# MRCS-Occupancy-Display.net
KiCad netlist of a schematic drawn in EAGLE
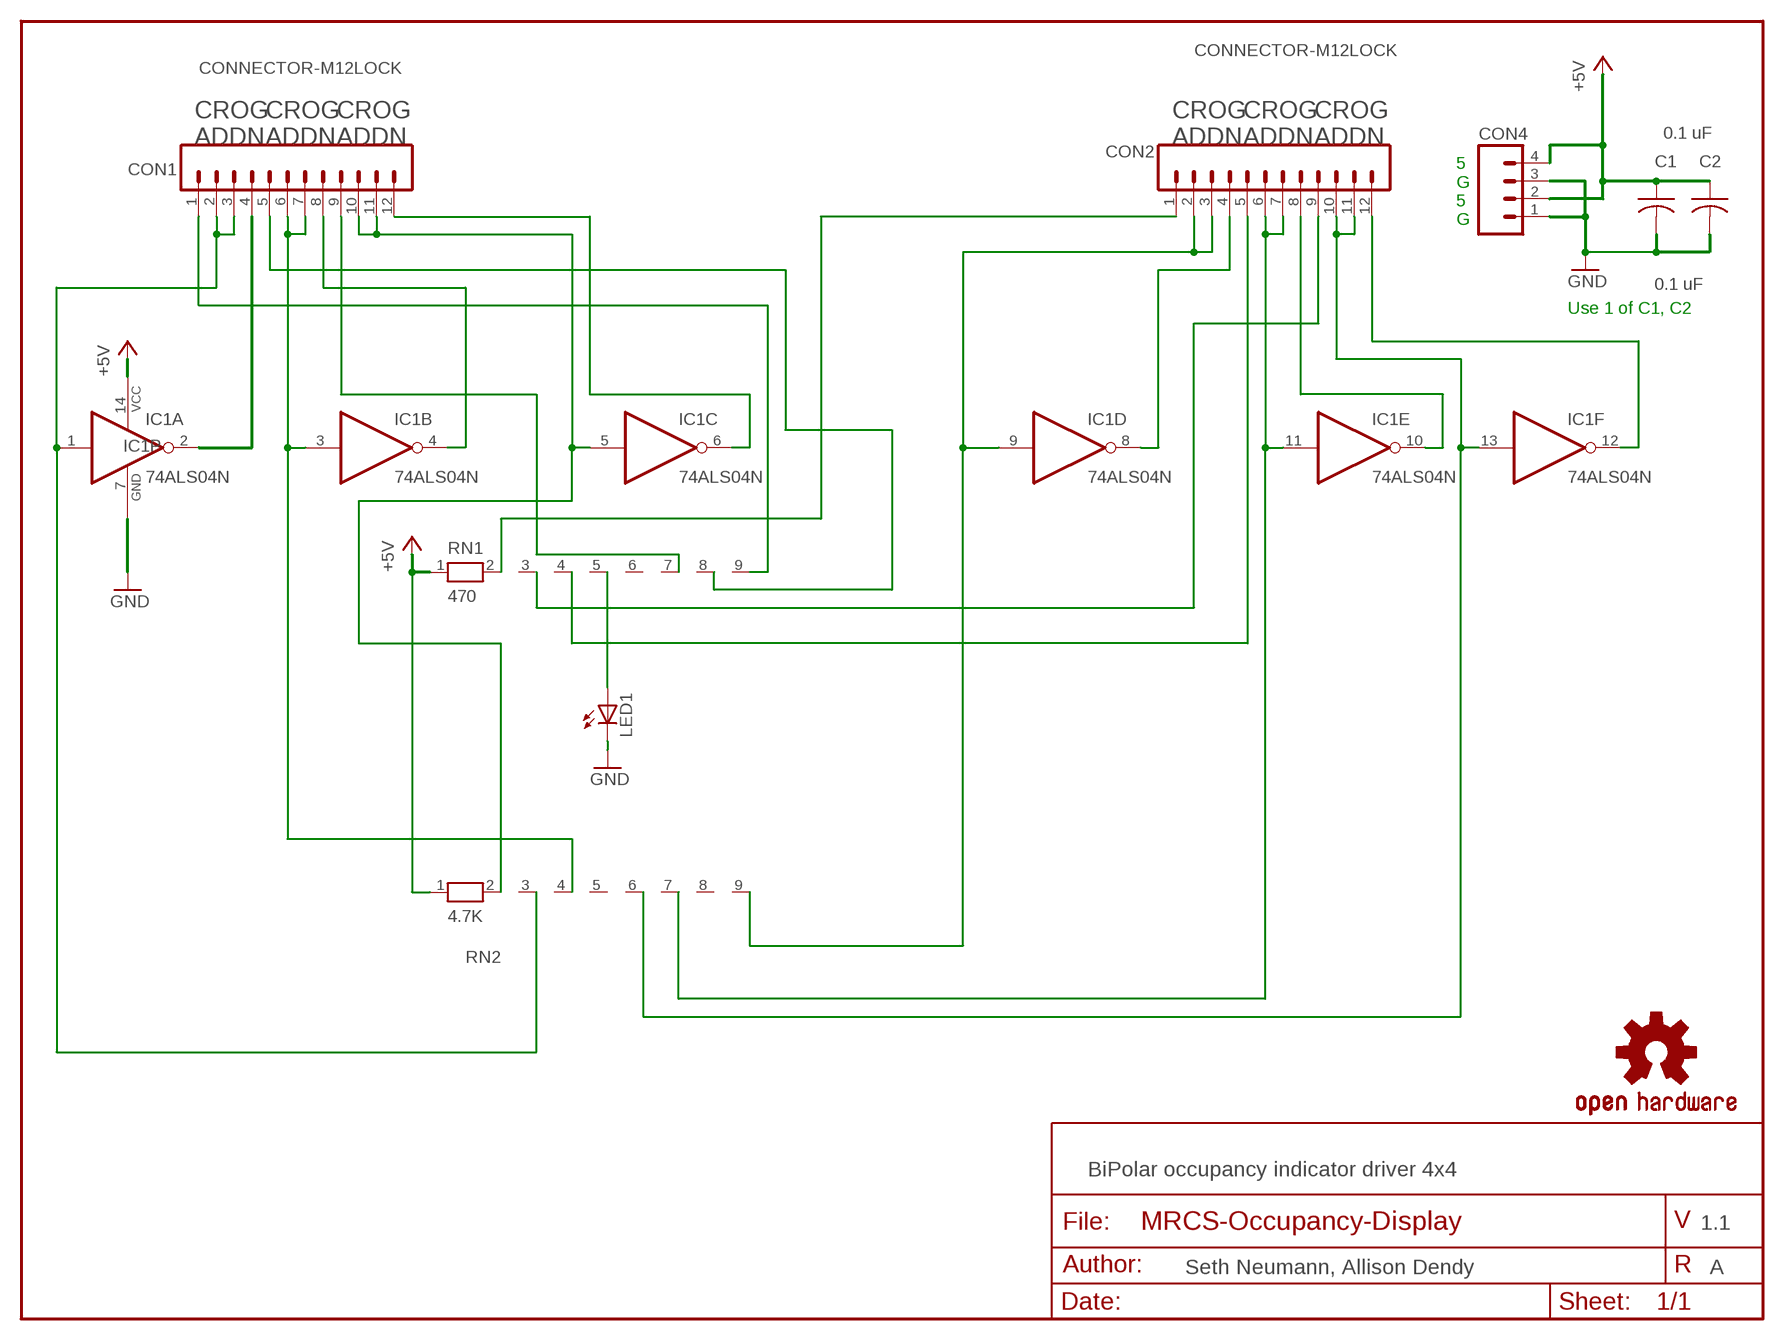
[diagram p0: schematic, sheet 1]

(export (version "E")
  (design (tool "Eeschema 10.0.6"))
  (components
    (comp (ref "C1")
      (value "0.1 uF")
      (footprint "eagle-import:C-PTH-0.100")
      (libsource (lib "eagle-import") (part "CAPPTH2"))
    )
    (comp (ref "C2")
      (value "0.1 uF")
      (footprint "eagle-import:C050-024X044")
      (libsource (lib "eagle-import") (part "CAPPTH1"))
    )
    (comp (ref "CON1")
      (value "CONNECTOR-M12LOCK")
      (footprint "eagle-import:1X12_LOCK")
      (libsource (lib "eagle-import") (part "CONNECTOR-M12LOCK"))
    )
    (comp (ref "CON2")
      (value "CONNECTOR-M12LOCK")
      (footprint "eagle-import:1X12_LOCK")
      (libsource (lib "eagle-import") (part "CONNECTOR-M12LOCK"))
    )
    (comp (ref "CON4")
      (value "CONNECTOR-M04SCREW")
      (footprint "eagle-import:SCREWTERMINAL-3.5MM-4")
      (libsource (lib "eagle-import") (part "CONNECTOR-M04SCREW"))
    )
    (comp (ref "IC1")
      (value "74ALS04N")
      (footprint "eagle-import:DIL14")
      (libsource (lib "eagle-import") (part "7404NALS"))
    )
    (comp (ref "LED1")
      (value "LEDLED3MM")
      (footprint "eagle-import:LED3MM")
      (libsource (lib "eagle-import") (part "LEDLED3MM"))
    )
    (comp (ref "OSHW1")
      (value "DOC-OSHW-LOGO-M")
      (footprint "eagle-import:OSHW-LOGO-M")
      (libsource (lib "eagle-import") (part "DOC-OSHW-LOGO-M"))
    )
    (comp (ref "RN1")
      (value "470")
      (footprint "eagle-import:RN-9")
      (libsource (lib "eagle-import") (part "RN08"))
    )
    (comp (ref "RN2")
      (value "4.7K")
      (footprint "eagle-import:RN-9")
      (libsource (lib "eagle-import") (part "RN08"))
    )
  )
  (nets
    (net (code "1") (name "+5V") (class "Default")
      (node (ref "C1") (pin "1") (pinfunction "1_1") (pintype "passive"))
      (node (ref "C2") (pin "1") (pinfunction "1_1") (pintype "passive"))
      (node (ref "CON4") (pin "2") (pinfunction "2_2") (pintype "passive"))
      (node (ref "CON4") (pin "4") (pinfunction "4_4") (pintype "passive"))
      (node (ref "IC1") (pin "14") (pinfunction "VCC_14") (pintype "power_in"))
      (node (ref "RN1") (pin "1") (pinfunction "1_1") (pintype "passive"))
      (node (ref "RN2") (pin "1") (pinfunction "1_1") (pintype "passive"))
    )
    (net (code "2") (name "GND") (class "Default")
      (node (ref "C1") (pin "2") (pinfunction "2_2") (pintype "passive"))
      (node (ref "C2") (pin "2") (pinfunction "2_2") (pintype "passive"))
      (node (ref "CON4") (pin "1") (pinfunction "1_1") (pintype "passive"))
      (node (ref "CON4") (pin "3") (pinfunction "3_3") (pintype "passive"))
      (node (ref "IC1") (pin "7") (pinfunction "GND_7") (pintype "power_in"))
      (node (ref "LED1") (pin "K") (pinfunction "C_K") (pintype "passive"))
    )
    (net (code "3") (name "Net-(CON1-Pad1)") (class "Default")
      (node (ref "CON1") (pin "1") (pinfunction "1_1") (pintype "passive"))
      (node (ref "RN1") (pin "9") (pinfunction "9_9") (pintype "passive"))
    )
    (net (code "4") (name "Net-(CON1-Pad5)") (class "Default")
      (node (ref "CON1") (pin "5") (pinfunction "5_5") (pintype "passive"))
      (node (ref "RN1") (pin "8") (pinfunction "8_8") (pintype "passive"))
    )
    (net (code "5") (name "Net-(CON1-Pad9)") (class "Default")
      (node (ref "CON1") (pin "9") (pinfunction "9_9") (pintype "passive"))
      (node (ref "RN1") (pin "7") (pinfunction "7_7") (pintype "passive"))
    )
    (net (code "6") (name "Net-(CON2-Pad1)") (class "Default")
      (node (ref "CON2") (pin "1") (pinfunction "1_1") (pintype "passive"))
      (node (ref "RN1") (pin "2") (pinfunction "2_2") (pintype "passive"))
    )
    (net (code "7") (name "Net-(CON2-Pad5)") (class "Default")
      (node (ref "CON2") (pin "5") (pinfunction "5_5") (pintype "passive"))
      (node (ref "RN1") (pin "4") (pinfunction "4_4") (pintype "passive"))
    )
    (net (code "8") (name "Net-(CON2-Pad9)") (class "Default")
      (node (ref "CON2") (pin "9") (pinfunction "9_9") (pintype "passive"))
      (node (ref "RN1") (pin "3") (pinfunction "3_3") (pintype "passive"))
    )
    (net (code "9") (name "Net-(IC1A-I)") (class "Default")
      (node (ref "CON1") (pin "2") (pinfunction "2_2") (pintype "passive"))
      (node (ref "CON1") (pin "3") (pinfunction "3_3") (pintype "passive"))
      (node (ref "IC1") (pin "1") (pinfunction "I_1") (pintype "input"))
      (node (ref "RN2") (pin "3") (pinfunction "3_3") (pintype "passive"))
    )
    (net (code "10") (name "Net-(IC1A-O)") (class "Default")
      (node (ref "CON1") (pin "4") (pinfunction "4_4") (pintype "passive"))
      (node (ref "IC1") (pin "2") (pinfunction "O_2") (pintype "output"))
    )
    (net (code "11") (name "Net-(IC1B-I)") (class "Default")
      (node (ref "CON1") (pin "6") (pinfunction "6_6") (pintype "passive"))
      (node (ref "CON1") (pin "7") (pinfunction "7_7") (pintype "passive"))
      (node (ref "IC1") (pin "3") (pinfunction "I_3") (pintype "input"))
      (node (ref "RN2") (pin "4") (pinfunction "4_4") (pintype "passive"))
    )
    (net (code "12") (name "Net-(IC1B-O)") (class "Default")
      (node (ref "CON1") (pin "8") (pinfunction "8_8") (pintype "passive"))
      (node (ref "IC1") (pin "4") (pinfunction "O_4") (pintype "output"))
    )
    (net (code "13") (name "Net-(IC1C-I)") (class "Default")
      (node (ref "CON1") (pin "10") (pinfunction "10_10") (pintype "passive"))
      (node (ref "CON1") (pin "11") (pinfunction "11_11") (pintype "passive"))
      (node (ref "IC1") (pin "5") (pinfunction "I_5") (pintype "input"))
      (node (ref "RN2") (pin "2") (pinfunction "2_2") (pintype "passive"))
    )
    (net (code "14") (name "Net-(IC1C-O)") (class "Default")
      (node (ref "CON1") (pin "12") (pinfunction "12_12") (pintype "passive"))
      (node (ref "IC1") (pin "6") (pinfunction "O_6") (pintype "output"))
    )
    (net (code "15") (name "Net-(IC1D-I)") (class "Default")
      (node (ref "CON2") (pin "2") (pinfunction "2_2") (pintype "passive"))
      (node (ref "CON2") (pin "3") (pinfunction "3_3") (pintype "passive"))
      (node (ref "IC1") (pin "9") (pinfunction "I_9") (pintype "input"))
      (node (ref "RN2") (pin "9") (pinfunction "9_9") (pintype "passive"))
    )
    (net (code "16") (name "Net-(IC1D-O)") (class "Default")
      (node (ref "CON2") (pin "4") (pinfunction "4_4") (pintype "passive"))
      (node (ref "IC1") (pin "8") (pinfunction "O_8") (pintype "output"))
    )
    (net (code "17") (name "Net-(IC1E-I)") (class "Default")
      (node (ref "CON2") (pin "6") (pinfunction "6_6") (pintype "passive"))
      (node (ref "CON2") (pin "7") (pinfunction "7_7") (pintype "passive"))
      (node (ref "IC1") (pin "11") (pinfunction "I_11") (pintype "input"))
      (node (ref "RN2") (pin "7") (pinfunction "7_7") (pintype "passive"))
    )
    (net (code "18") (name "Net-(IC1E-O)") (class "Default")
      (node (ref "CON2") (pin "8") (pinfunction "8_8") (pintype "passive"))
      (node (ref "IC1") (pin "10") (pinfunction "O_10") (pintype "output"))
    )
    (net (code "19") (name "Net-(IC1F-I)") (class "Default")
      (node (ref "CON2") (pin "10") (pinfunction "10_10") (pintype "passive"))
      (node (ref "CON2") (pin "11") (pinfunction "11_11") (pintype "passive"))
      (node (ref "IC1") (pin "13") (pinfunction "I_13") (pintype "input"))
      (node (ref "RN2") (pin "6") (pinfunction "6_6") (pintype "passive"))
    )
    (net (code "20") (name "Net-(IC1F-O)") (class "Default")
      (node (ref "CON2") (pin "12") (pinfunction "12_12") (pintype "passive"))
      (node (ref "IC1") (pin "12") (pinfunction "O_12") (pintype "output"))
    )
    (net (code "21") (name "Net-(LED1-PadA)") (class "Default")
      (node (ref "LED1") (pin "A") (pinfunction "A_A") (pintype "passive"))
      (node (ref "RN1") (pin "5") (pinfunction "5_5") (pintype "passive"))
    )
    (net (code "22") (name "unconnected-(RN1-Pad6)") (class "Default")
      (node (ref "RN1") (pin "6") (pinfunction "6_6") (pintype "passive"))
    )
    (net (code "23") (name "unconnected-(RN2-Pad5)") (class "Default")
      (node (ref "RN2") (pin "5") (pinfunction "5_5") (pintype "passive"))
    )
    (net (code "24") (name "unconnected-(RN2-Pad8)") (class "Default")
      (node (ref "RN2") (pin "8") (pinfunction "8_8") (pintype "passive"))
    )
  )
)
